# LaserPowerMeter.net
KiCad netlist of a schematic drawn in EAGLE
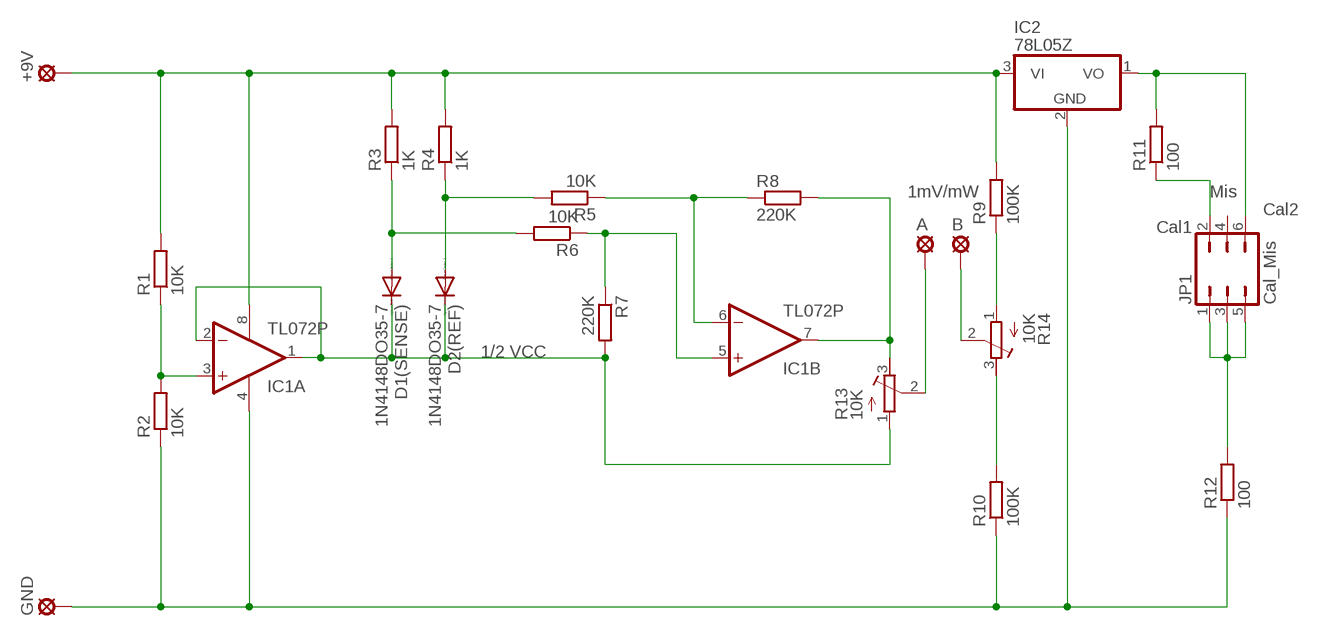
[diagram p0: schematic, sheet 1]

(export (version "E")
  (design (tool "Eeschema 10.0.6"))
  (components
    (comp (ref "+9V")
      (value "LSP10")
      (footprint "eagle-import:LSP10")
      (libsource (lib "eagle-import") (part "LSP10"))
    )
    (comp (ref "A")
      (value "LSP10")
      (footprint "eagle-import:LSP10")
      (libsource (lib "eagle-import") (part "LSP10"))
    )
    (comp (ref "B")
      (value "LSP10")
      (footprint "eagle-import:LSP10")
      (libsource (lib "eagle-import") (part "LSP10"))
    )
    (comp (ref "D1(SENSE)")
      (value "1N4148DO35-7")
      (footprint "eagle-import:DO35-7")
      (libsource (lib "eagle-import") (part "1N4148DO35-7"))
    )
    (comp (ref "D2(REF)")
      (value "1N4148DO35-7")
      (footprint "eagle-import:DO35-7")
      (libsource (lib "eagle-import") (part "1N4148DO35-7"))
    )
    (comp (ref "GND")
      (value "LSP10")
      (footprint "eagle-import:LSP10")
      (libsource (lib "eagle-import") (part "LSP10"))
    )
    (comp (ref "IC1")
      (value "TL072P")
      (footprint "eagle-import:DIL08")
      (libsource (lib "eagle-import") (part "TL072P"))
    )
    (comp (ref "IC2")
      (value "78L05Z")
      (footprint "eagle-import:TO92")
      (libsource (lib "eagle-import") (part "78ZL05"))
    )
    (comp (ref "JP1")
      (value "Cal_Mis")
      (footprint "eagle-import:JP3Q")
      (libsource (lib "eagle-import") (part "JP3Q"))
    )
    (comp (ref "R1")
      (value "10K")
      (footprint "eagle-import:0204_7")
      (libsource (lib "eagle-import") (part "R-EU_0204/7"))
    )
    (comp (ref "R2")
      (value "10K")
      (footprint "eagle-import:0204_7")
      (libsource (lib "eagle-import") (part "R-EU_0204/7"))
    )
    (comp (ref "R3")
      (value "1K")
      (footprint "eagle-import:0204_7")
      (libsource (lib "eagle-import") (part "R-EU_0204/7"))
    )
    (comp (ref "R4")
      (value "1K")
      (footprint "eagle-import:0204_7")
      (libsource (lib "eagle-import") (part "R-EU_0204/7"))
    )
    (comp (ref "R5")
      (value "10K")
      (footprint "eagle-import:0204_7")
      (libsource (lib "eagle-import") (part "R-EU_0204/7"))
    )
    (comp (ref "R6")
      (value "10K")
      (footprint "eagle-import:0204_7")
      (libsource (lib "eagle-import") (part "R-EU_0204/7"))
    )
    (comp (ref "R7")
      (value "220K")
      (footprint "eagle-import:0204_7")
      (libsource (lib "eagle-import") (part "R-EU_0204/7"))
    )
    (comp (ref "R8")
      (value "220K")
      (footprint "eagle-import:0204_7")
      (libsource (lib "eagle-import") (part "R-EU_0204/7"))
    )
    (comp (ref "R9")
      (value "100K")
      (footprint "eagle-import:0204_7")
      (libsource (lib "eagle-import") (part "R-EU_0204/7"))
    )
    (comp (ref "R10")
      (value "100K")
      (footprint "eagle-import:0204_7")
      (libsource (lib "eagle-import") (part "R-EU_0204/7"))
    )
    (comp (ref "R11")
      (value "100")
      (footprint "eagle-import:0204_7")
      (libsource (lib "eagle-import") (part "R-EU_0204/7"))
    )
    (comp (ref "R12")
      (value "100")
      (footprint "eagle-import:0204_7")
      (libsource (lib "eagle-import") (part "R-EU_0204/7"))
    )
    (comp (ref "R13")
      (value "10K")
      (footprint "eagle-import:RTRIM3339P")
      (libsource (lib "eagle-import") (part "R-TRIMM3339P"))
    )
    (comp (ref "R14")
      (value "10K")
      (footprint "eagle-import:RTRIM3339P")
      (libsource (lib "eagle-import") (part "R-TRIMM3339P"))
    )
  )
  (nets
    (net (code "1") (name "Net-(D1(SENSE)-PadA)") (class "Default")
      (node (ref "D1(SENSE)") (pin "A") (pinfunction "A_A") (pintype "passive"))
      (node (ref "R3") (pin "1") (pinfunction "1_1") (pintype "passive"))
      (node (ref "R6") (pin "2") (pinfunction "2_2") (pintype "passive"))
    )
    (net (code "2") (name "Net-(D2(REF)-PadA)") (class "Default")
      (node (ref "D2(REF)") (pin "A") (pinfunction "A_A") (pintype "passive"))
      (node (ref "R4") (pin "1") (pinfunction "1_1") (pintype "passive"))
      (node (ref "R5") (pin "2") (pinfunction "2_2") (pintype "passive"))
    )
    (net (code "3") (name "Net-(IC1A-+IN)") (class "Default")
      (node (ref "IC1") (pin "3") (pinfunction "+IN_3") (pintype "input"))
      (node (ref "R1") (pin "1") (pinfunction "1_1") (pintype "passive"))
      (node (ref "R2") (pin "2") (pinfunction "2_2") (pintype "passive"))
    )
    (net (code "4") (name "Net-(IC1A--IN)") (class "Default")
      (node (ref "D1(SENSE)") (pin "C") (pinfunction "C_C") (pintype "passive"))
      (node (ref "D2(REF)") (pin "C") (pinfunction "C_C") (pintype "passive"))
      (node (ref "IC1") (pin "1") (pinfunction "OUT_1") (pintype "output"))
      (node (ref "IC1") (pin "2") (pinfunction "-IN_2") (pintype "input"))
      (node (ref "R13") (pin "1") (pinfunction "A_1") (pintype "passive"))
      (node (ref "R7") (pin "2") (pinfunction "2_2") (pintype "passive"))
    )
    (net (code "5") (name "Net-(IC1B-+IN)") (class "Default")
      (node (ref "IC1") (pin "5") (pinfunction "+IN_5") (pintype "input"))
      (node (ref "R6") (pin "1") (pinfunction "1_1") (pintype "passive"))
      (node (ref "R7") (pin "1") (pinfunction "1_1") (pintype "passive"))
    )
    (net (code "6") (name "Net-(IC1B--IN)") (class "Default")
      (node (ref "IC1") (pin "6") (pinfunction "-IN_6") (pintype "input"))
      (node (ref "R5") (pin "1") (pinfunction "1_1") (pintype "passive"))
      (node (ref "R8") (pin "1") (pinfunction "1_1") (pintype "passive"))
    )
    (net (code "7") (name "Net-(IC1B-OUT)") (class "Default")
      (node (ref "IC1") (pin "7") (pinfunction "OUT_7") (pintype "output"))
      (node (ref "R13") (pin "3") (pinfunction "E_3") (pintype "passive"))
      (node (ref "R8") (pin "2") (pinfunction "2_2") (pintype "passive"))
    )
    (net (code "8") (name "Net-(IC1C-V+)") (class "Default")
      (node (ref "+9V") (pin "MP") (pinfunction "MP_MP") (pintype "passive"))
      (node (ref "IC1") (pin "8") (pinfunction "V+_8") (pintype "power_in"))
      (node (ref "IC2") (pin "3") (pinfunction "VI_3") (pintype "input"))
      (node (ref "R1") (pin "2") (pinfunction "2_2") (pintype "passive"))
      (node (ref "R3") (pin "2") (pinfunction "2_2") (pintype "passive"))
      (node (ref "R4") (pin "2") (pinfunction "2_2") (pintype "passive"))
      (node (ref "R9") (pin "2") (pinfunction "2_2") (pintype "passive"))
    )
    (net (code "9") (name "Net-(IC1C-V-)") (class "Default")
      (node (ref "GND") (pin "MP") (pinfunction "MP_MP") (pintype "passive"))
      (node (ref "IC1") (pin "4") (pinfunction "V-_4") (pintype "power_in"))
      (node (ref "IC2") (pin "2") (pinfunction "GND_2") (pintype "passive"))
      (node (ref "R10") (pin "1") (pinfunction "1_1") (pintype "passive"))
      (node (ref "R12") (pin "1") (pinfunction "1_1") (pintype "passive"))
      (node (ref "R2") (pin "1") (pinfunction "1_1") (pintype "passive"))
    )
    (net (code "10") (name "Net-(IC2-VO)") (class "Default")
      (node (ref "IC2") (pin "1") (pinfunction "VO_1") (pintype "passive"))
      (node (ref "JP1") (pin "6") (pinfunction "6_6") (pintype "passive"))
      (node (ref "R11") (pin "2") (pinfunction "2_2") (pintype "passive"))
    )
    (net (code "11") (name "Net-(JP1-Pad1)") (class "Default")
      (node (ref "JP1") (pin "1") (pinfunction "1_1") (pintype "passive"))
      (node (ref "JP1") (pin "3") (pinfunction "3_3") (pintype "passive"))
      (node (ref "JP1") (pin "5") (pinfunction "5_5") (pintype "passive"))
      (node (ref "R12") (pin "2") (pinfunction "2_2") (pintype "passive"))
    )
    (net (code "12") (name "Net-(JP1-Pad2)") (class "Default")
      (node (ref "JP1") (pin "2") (pinfunction "2_2") (pintype "passive"))
      (node (ref "R11") (pin "1") (pinfunction "1_1") (pintype "passive"))
    )
    (net (code "13") (name "Net-(R13-S)") (class "Default")
      (node (ref "A") (pin "MP") (pinfunction "MP_MP") (pintype "passive"))
      (node (ref "R13") (pin "2") (pinfunction "S_2") (pintype "passive"))
    )
    (net (code "14") (name "Net-(R14-A)") (class "Default")
      (node (ref "R14") (pin "1") (pinfunction "A_1") (pintype "passive"))
      (node (ref "R9") (pin "1") (pinfunction "1_1") (pintype "passive"))
    )
    (net (code "15") (name "Net-(R14-E)") (class "Default")
      (node (ref "R10") (pin "2") (pinfunction "2_2") (pintype "passive"))
      (node (ref "R14") (pin "3") (pinfunction "E_3") (pintype "passive"))
    )
    (net (code "16") (name "Net-(R14-S)") (class "Default")
      (node (ref "B") (pin "MP") (pinfunction "MP_MP") (pintype "passive"))
      (node (ref "R14") (pin "2") (pinfunction "S_2") (pintype "passive"))
    )
    (net (code "17") (name "unconnected-(JP1-Pad4)") (class "Default")
      (node (ref "JP1") (pin "4") (pinfunction "4_4") (pintype "passive"))
    )
  )
)
